# dpdt_switch_breakout.net
KiCad netlist of a schematic drawn in EAGLE
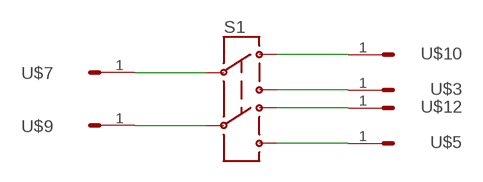
[diagram p0: schematic, sheet 1]

(export (version "E")
  (design (tool "Eeschema 10.0.6"))
  (components
    (comp (ref "S1")
      (value "SWITCH-DPDTPTH1")
      (footprint "eagle-import:SWITCH-DPDT_SUBMINIATURE")
      (libsource (lib "eagle-import") (part "SWITCH-DPDTPTH1"))
    )
    (comp (ref "U$3")
      (value "HEADER/MALE/01NOBORDER")
      (footprint "eagle-import:HEADER_MALE_01_NOBORDER")
      (libsource (lib "eagle-import") (part "HEADER/MALE/01NOBORDER"))
    )
    (comp (ref "U$5")
      (value "HEADER/MALE/01NOBORDER")
      (footprint "eagle-import:HEADER_MALE_01_NOBORDER")
      (libsource (lib "eagle-import") (part "HEADER/MALE/01NOBORDER"))
    )
    (comp (ref "U$7")
      (value "HEADER/MALE/01NOBORDER")
      (footprint "eagle-import:HEADER_MALE_01_NOBORDER")
      (libsource (lib "eagle-import") (part "HEADER/MALE/01NOBORDER"))
    )
    (comp (ref "U$9")
      (value "HEADER/MALE/01NOBORDER")
      (footprint "eagle-import:HEADER_MALE_01_NOBORDER")
      (libsource (lib "eagle-import") (part "HEADER/MALE/01NOBORDER"))
    )
    (comp (ref "U$10")
      (value "HEADER/MALE/01NOBORDER")
      (footprint "eagle-import:HEADER_MALE_01_NOBORDER")
      (libsource (lib "eagle-import") (part "HEADER/MALE/01NOBORDER"))
    )
    (comp (ref "U$12")
      (value "HEADER/MALE/01NOBORDER")
      (footprint "eagle-import:HEADER_MALE_01_NOBORDER")
      (libsource (lib "eagle-import") (part "HEADER/MALE/01NOBORDER"))
    )
  )
  (nets
    (net (code "1") (name "Net-(U$3-3)") (class "Default")
      (node (ref "S1") (pin "3") (pinfunction "3_3") (pintype "bidirectional"))
      (node (ref "U$3") (pin "1") (pinfunction "3_1") (pintype "passive"))
    )
    (net (code "2") (name "Net-(U$5-3)") (class "Default")
      (node (ref "S1") (pin "6") (pinfunction "6_6") (pintype "bidirectional"))
      (node (ref "U$5") (pin "1") (pinfunction "3_1") (pintype "passive"))
    )
    (net (code "3") (name "Net-(U$7-3)") (class "Default")
      (node (ref "S1") (pin "2") (pinfunction "2_2") (pintype "bidirectional"))
      (node (ref "U$7") (pin "1") (pinfunction "3_1") (pintype "passive"))
    )
    (net (code "4") (name "Net-(U$9-3)") (class "Default")
      (node (ref "S1") (pin "5") (pinfunction "5_5") (pintype "bidirectional"))
      (node (ref "U$9") (pin "1") (pinfunction "3_1") (pintype "passive"))
    )
    (net (code "5") (name "Net-(U$10-3)") (class "Default")
      (node (ref "S1") (pin "1") (pinfunction "1_1") (pintype "bidirectional"))
      (node (ref "U$10") (pin "1") (pinfunction "3_1") (pintype "passive"))
    )
    (net (code "6") (name "Net-(U$12-3)") (class "Default")
      (node (ref "S1") (pin "4") (pinfunction "4_4") (pintype "bidirectional"))
      (node (ref "U$12") (pin "1") (pinfunction "3_1") (pintype "passive"))
    )
  )
)
